# ATEM_TALLY_BOARD_102912.net
KiCad netlist of a schematic drawn in EAGLE
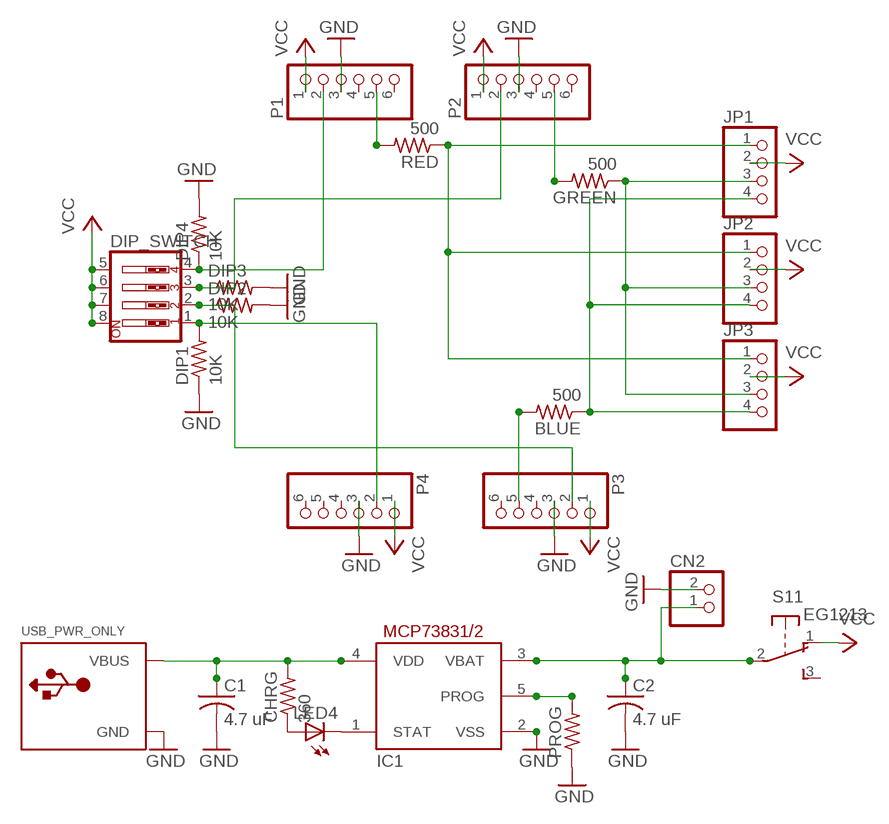
[diagram p0: schematic, sheet 1]

(export (version "E")
  (design (tool "Eeschema 10.0.6"))
  (components
    (comp (ref "BLUE")
      (value "500")
      (footprint "eagle-import:R0805")
      (libsource (lib "eagle-import") (part "R-US_R0805"))
    )
    (comp (ref "C1")
      (value "4.7 uF")
      (footprint "eagle-import:C0805K")
      (libsource (lib "eagle-import") (part "C-USC0805K"))
    )
    (comp (ref "C2")
      (value "4.7 uF")
      (footprint "eagle-import:C0805K")
      (libsource (lib "eagle-import") (part "C-USC0805K"))
    )
    (comp (ref "CHRG")
      (value "360")
      (footprint "eagle-import:R0805")
      (libsource (lib "eagle-import") (part "R-US_R0805"))
    )
    (comp (ref "CN2")
      (value "JST_2PIN-SMT-RA")
      (footprint "eagle-import:JST-PH-2-SMT-RA")
      (libsource (lib "eagle-import") (part "JST_2PIN-SMT-RA"))
    )
    (comp (ref "DIP1")
      (value "10K")
      (footprint "eagle-import:R0805")
      (libsource (lib "eagle-import") (part "R-US_R0805"))
    )
    (comp (ref "DIP2")
      (value "10K")
      (footprint "eagle-import:R0805")
      (libsource (lib "eagle-import") (part "R-US_R0805"))
    )
    (comp (ref "DIP3")
      (value "10K")
      (footprint "eagle-import:R0805")
      (libsource (lib "eagle-import") (part "R-US_R0805"))
    )
    (comp (ref "DIP4")
      (value "10K")
      (footprint "eagle-import:R0805")
      (libsource (lib "eagle-import") (part "R-US_R0805"))
    )
    (comp (ref "DIP_SWITCH")
      (value "SW_DIP-4")
      (footprint "eagle-import:EDG-04")
      (libsource (lib "eagle-import") (part "SW_DIP-4"))
    )
    (comp (ref "GREEN")
      (value "500")
      (footprint "eagle-import:R0805")
      (libsource (lib "eagle-import") (part "R-US_R0805"))
    )
    (comp (ref "IC1")
      (value "MCP73831/OT")
      (footprint "eagle-import:SOT23-5L")
      (libsource (lib "eagle-import") (part "MCP73831/OT"))
    )
    (comp (ref "JP1")
      (value "PINHD-1X4")
      (footprint "eagle-import:1X04")
      (libsource (lib "eagle-import") (part "PINHD-1X4"))
    )
    (comp (ref "JP2")
      (value "PINHD-1X4")
      (footprint "eagle-import:1X04")
      (libsource (lib "eagle-import") (part "PINHD-1X4"))
    )
    (comp (ref "JP3")
      (value "PINHD-1X4")
      (footprint "eagle-import:1X04")
      (libsource (lib "eagle-import") (part "PINHD-1X4"))
    )
    (comp (ref "LED4")
      (value "LED3MM")
      (footprint "eagle-import:LED3MM")
      (libsource (lib "eagle-import") (part "LED3MM"))
    )
    (comp (ref "P1")
      (value "PINHD-1X6CB")
      (footprint "eagle-import:1X06-CLEANBIG")
      (libsource (lib "eagle-import") (part "PINHD-1X6CB"))
    )
    (comp (ref "P2")
      (value "PINHD-1X6CB")
      (footprint "eagle-import:1X06-CLEANBIG")
      (libsource (lib "eagle-import") (part "PINHD-1X6CB"))
    )
    (comp (ref "P3")
      (value "PINHD-1X6CB")
      (footprint "eagle-import:1X06-CLEANBIG")
      (libsource (lib "eagle-import") (part "PINHD-1X6CB"))
    )
    (comp (ref "P4")
      (value "PINHD-1X6CB")
      (footprint "eagle-import:1X06-CLEANBIG")
      (libsource (lib "eagle-import") (part "PINHD-1X6CB"))
    )
    (comp (ref "PROG")
      (value "R-US_R0805")
      (footprint "eagle-import:R0805")
      (libsource (lib "eagle-import") (part "R-US_R0805"))
    )
    (comp (ref "RED")
      (value "500")
      (footprint "eagle-import:R0805")
      (libsource (lib "eagle-import") (part "R-US_R0805"))
    )
    (comp (ref "S1")
      (value "EG1213")
      (footprint "eagle-import:EG1213")
      (libsource (lib "eagle-import") (part "EG1213"))
    )
    (comp (ref "USB_PWR_ONLY")
      (value "USB-PWR-NOSILK")
      (footprint "eagle-import:USB-MINIB-THM-MOLEX-PWRONLY-NOSILK")
      (libsource (lib "eagle-import") (part "USB-PWR-NOSILK"))
    )
  )
  (nets
    (net (code "1") (name "GND") (class "Default")
      (node (ref "C1") (pin "2") (pinfunction "2_2") (pintype "passive"))
      (node (ref "C2") (pin "2") (pinfunction "2_2") (pintype "passive"))
      (node (ref "CN2") (pin "2") (pinfunction "1_2") (pintype "passive"))
      (node (ref "DIP1") (pin "1") (pinfunction "1_1") (pintype "passive"))
      (node (ref "DIP2") (pin "2") (pinfunction "2_2") (pintype "passive"))
      (node (ref "DIP3") (pin "2") (pinfunction "2_2") (pintype "passive"))
      (node (ref "DIP4") (pin "2") (pinfunction "2_2") (pintype "passive"))
      (node (ref "IC1") (pin "2") (pinfunction "VSS_2") (pintype "power_in"))
      (node (ref "P1") (pin "3") (pinfunction "3_3") (pintype "passive"))
      (node (ref "P2") (pin "3") (pinfunction "3_3") (pintype "passive"))
      (node (ref "P3") (pin "3") (pinfunction "3_3") (pintype "passive"))
      (node (ref "P4") (pin "3") (pinfunction "3_3") (pintype "passive"))
      (node (ref "PROG") (pin "1") (pinfunction "1_1") (pintype "passive"))
      (node (ref "USB_PWR_ONLY") (pin "GND") (pinfunction "GND_GND") (pintype "power_in"))
    )
    (net (code "2") (name "Net-(BLUE-Pad1)") (class "Default")
      (node (ref "BLUE") (pin "1") (pinfunction "1_1") (pintype "passive"))
      (node (ref "JP1") (pin "4") (pinfunction "4_4") (pintype "passive"))
      (node (ref "JP2") (pin "4") (pinfunction "4_4") (pintype "passive"))
      (node (ref "JP3") (pin "4") (pinfunction "4_4") (pintype "passive"))
    )
    (net (code "3") (name "Net-(BLUE-Pad2)") (class "Default")
      (node (ref "BLUE") (pin "2") (pinfunction "2_2") (pintype "passive"))
      (node (ref "P3") (pin "5") (pinfunction "5_5") (pintype "passive"))
    )
    (net (code "4") (name "Net-(CHRG-Pad1)") (class "Default")
      (node (ref "CHRG") (pin "1") (pinfunction "1_1") (pintype "passive"))
      (node (ref "LED4") (pin "A") (pinfunction "A_A") (pintype "passive"))
    )
    (net (code "5") (name "Net-(CN2-2)") (class "Default")
      (node (ref "C2") (pin "1") (pinfunction "1_1") (pintype "passive"))
      (node (ref "CN2") (pin "1") (pinfunction "2_1") (pintype "passive"))
      (node (ref "IC1") (pin "3") (pinfunction "VBAT_3") (pintype "bidirectional"))
      (node (ref "S1") (pin "2") (pinfunction "P_2") (pintype "passive"))
    )
    (net (code "6") (name "Net-(DIP1-Pad2)") (class "Default")
      (node (ref "DIP1") (pin "2") (pinfunction "2_2") (pintype "passive"))
      (node (ref "DIP_SWITCH") (pin "1") (pinfunction "1_1") (pintype "passive"))
      (node (ref "P4") (pin "2") (pinfunction "2_2") (pintype "passive"))
    )
    (net (code "7") (name "Net-(DIP2-Pad1)") (class "Default")
      (node (ref "DIP2") (pin "1") (pinfunction "1_1") (pintype "passive"))
      (node (ref "DIP_SWITCH") (pin "2") (pinfunction "2_2") (pintype "passive"))
      (node (ref "P3") (pin "2") (pinfunction "2_2") (pintype "passive"))
    )
    (net (code "8") (name "Net-(DIP3-Pad1)") (class "Default")
      (node (ref "DIP3") (pin "1") (pinfunction "1_1") (pintype "passive"))
      (node (ref "DIP_SWITCH") (pin "3") (pinfunction "3_3") (pintype "passive"))
      (node (ref "P2") (pin "2") (pinfunction "2_2") (pintype "passive"))
    )
    (net (code "9") (name "Net-(DIP4-Pad1)") (class "Default")
      (node (ref "DIP4") (pin "1") (pinfunction "1_1") (pintype "passive"))
      (node (ref "DIP_SWITCH") (pin "4") (pinfunction "4_4") (pintype "passive"))
      (node (ref "P1") (pin "2") (pinfunction "2_2") (pintype "passive"))
    )
    (net (code "10") (name "Net-(GREEN-Pad1)") (class "Default")
      (node (ref "GREEN") (pin "1") (pinfunction "1_1") (pintype "passive"))
      (node (ref "JP1") (pin "3") (pinfunction "3_3") (pintype "passive"))
      (node (ref "JP2") (pin "3") (pinfunction "3_3") (pintype "passive"))
      (node (ref "JP3") (pin "3") (pinfunction "3_3") (pintype "passive"))
    )
    (net (code "11") (name "Net-(GREEN-Pad2)") (class "Default")
      (node (ref "GREEN") (pin "2") (pinfunction "2_2") (pintype "passive"))
      (node (ref "P2") (pin "5") (pinfunction "5_5") (pintype "passive"))
    )
    (net (code "12") (name "Net-(IC1-PROG)") (class "Default")
      (node (ref "IC1") (pin "5") (pinfunction "PROG_5") (pintype "input"))
      (node (ref "PROG") (pin "2") (pinfunction "2_2") (pintype "passive"))
    )
    (net (code "13") (name "Net-(IC1-STAT)") (class "Default")
      (node (ref "IC1") (pin "1") (pinfunction "STAT_1") (pintype "output"))
      (node (ref "LED4") (pin "K") (pinfunction "C_K") (pintype "passive"))
    )
    (net (code "14") (name "Net-(IC1-VDD)") (class "Default")
      (node (ref "C1") (pin "1") (pinfunction "1_1") (pintype "passive"))
      (node (ref "CHRG") (pin "2") (pinfunction "2_2") (pintype "passive"))
      (node (ref "IC1") (pin "4") (pinfunction "VDD_4") (pintype "power_in"))
      (node (ref "USB_PWR_ONLY") (pin "VBUS") (pinfunction "VBUS_VBUS") (pintype "power_in"))
    )
    (net (code "15") (name "Net-(JP1-Pad1)") (class "Default")
      (node (ref "JP1") (pin "1") (pinfunction "1_1") (pintype "passive"))
      (node (ref "JP2") (pin "1") (pinfunction "1_1") (pintype "passive"))
      (node (ref "JP3") (pin "1") (pinfunction "1_1") (pintype "passive"))
      (node (ref "RED") (pin "1") (pinfunction "1_1") (pintype "passive"))
    )
    (net (code "16") (name "Net-(P1-Pad5)") (class "Default")
      (node (ref "P1") (pin "5") (pinfunction "5_5") (pintype "passive"))
      (node (ref "RED") (pin "2") (pinfunction "2_2") (pintype "passive"))
    )
    (net (code "17") (name "VCC") (class "Default")
      (node (ref "DIP_SWITCH") (pin "5") (pinfunction "5_5") (pintype "passive"))
      (node (ref "DIP_SWITCH") (pin "6") (pinfunction "6_6") (pintype "passive"))
      (node (ref "DIP_SWITCH") (pin "7") (pinfunction "7_7") (pintype "passive"))
      (node (ref "DIP_SWITCH") (pin "8") (pinfunction "8_8") (pintype "passive"))
      (node (ref "JP1") (pin "2") (pinfunction "2_2") (pintype "passive"))
      (node (ref "JP2") (pin "2") (pinfunction "2_2") (pintype "passive"))
      (node (ref "JP3") (pin "2") (pinfunction "2_2") (pintype "passive"))
      (node (ref "P1") (pin "1") (pinfunction "1_1") (pintype "passive"))
      (node (ref "P2") (pin "1") (pinfunction "1_1") (pintype "passive"))
      (node (ref "P3") (pin "1") (pinfunction "1_1") (pintype "passive"))
      (node (ref "P4") (pin "1") (pinfunction "1_1") (pintype "passive"))
      (node (ref "S1") (pin "1") (pinfunction "O_1") (pintype "passive"))
    )
    (net (code "18") (name "unconnected-(P1-Pad4)") (class "Default")
      (node (ref "P1") (pin "4") (pinfunction "4_4") (pintype "passive"))
    )
    (net (code "19") (name "unconnected-(P1-Pad6)") (class "Default")
      (node (ref "P1") (pin "6") (pinfunction "6_6") (pintype "passive"))
    )
    (net (code "20") (name "unconnected-(P2-Pad4)") (class "Default")
      (node (ref "P2") (pin "4") (pinfunction "4_4") (pintype "passive"))
    )
    (net (code "21") (name "unconnected-(P2-Pad6)") (class "Default")
      (node (ref "P2") (pin "6") (pinfunction "6_6") (pintype "passive"))
    )
    (net (code "22") (name "unconnected-(P3-Pad4)") (class "Default")
      (node (ref "P3") (pin "4") (pinfunction "4_4") (pintype "passive"))
    )
    (net (code "23") (name "unconnected-(P3-Pad6)") (class "Default")
      (node (ref "P3") (pin "6") (pinfunction "6_6") (pintype "passive"))
    )
    (net (code "24") (name "unconnected-(P4-Pad4)") (class "Default")
      (node (ref "P4") (pin "4") (pinfunction "4_4") (pintype "passive"))
    )
    (net (code "25") (name "unconnected-(P4-Pad5)") (class "Default")
      (node (ref "P4") (pin "5") (pinfunction "5_5") (pintype "passive"))
    )
    (net (code "26") (name "unconnected-(P4-Pad6)") (class "Default")
      (node (ref "P4") (pin "6") (pinfunction "6_6") (pintype "passive"))
    )
    (net (code "27") (name "unconnected-(S1A-S-Pad3)") (class "Default")
      (node (ref "S1") (pin "3") (pinfunction "S_3") (pintype "passive"))
    )
  )
)
